# esp-rfid-relay-board.net
KiCad netlist of a schematic drawn in EAGLE
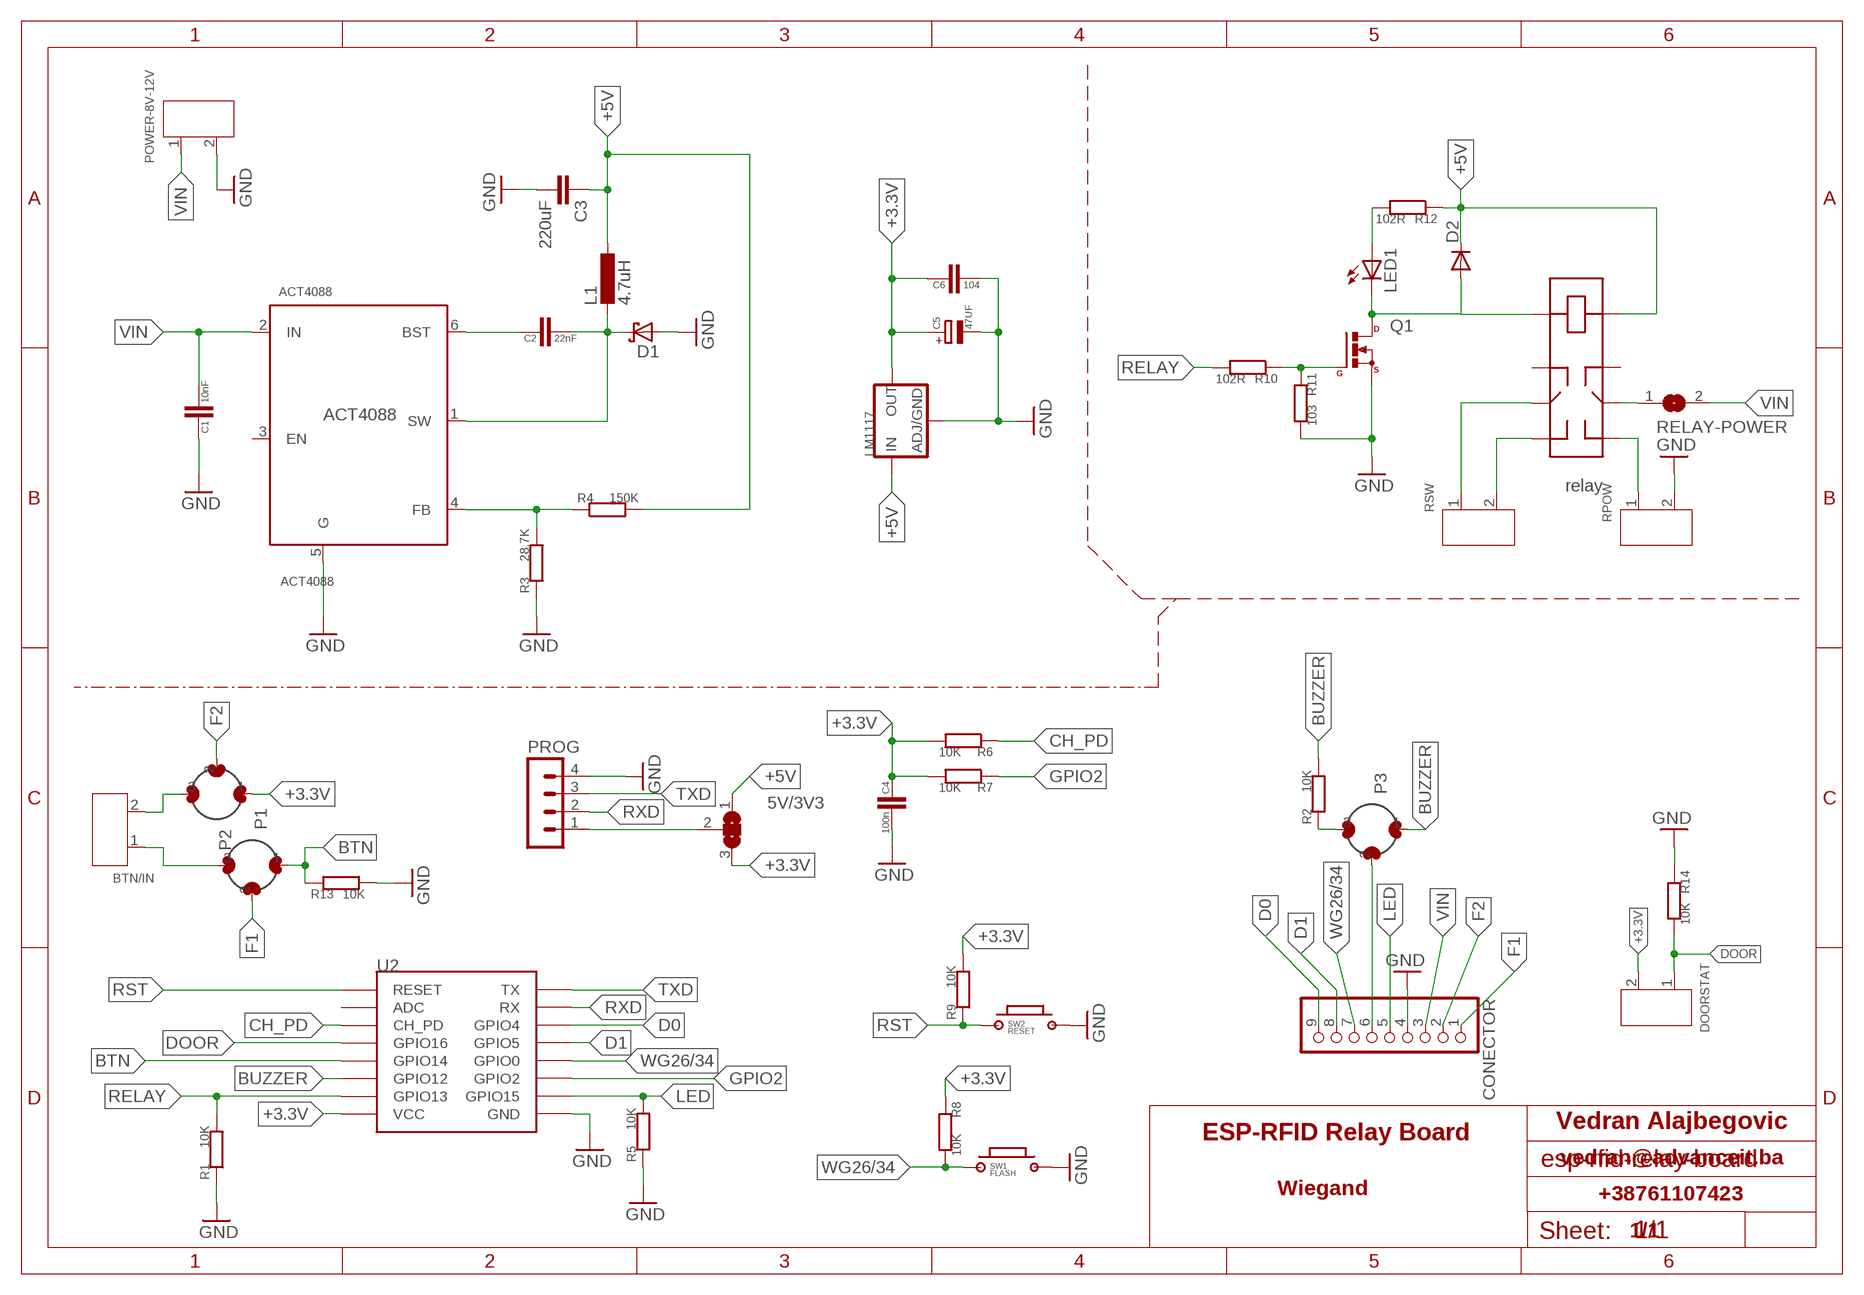
[diagram p0: schematic, sheet 1]

(export (version "E")
  (design (tool "Eeschema 10.0.6"))
  (components
    (comp (ref "5V/3V3")
      (value "SJ2W")
      (footprint "eagle-import:SJ_2")
      (libsource (lib "eagle-import") (part "SJ2W"))
    )
    (comp (ref "ACT4088")
      (value "ACT4088")
      (footprint "eagle-import:SOT-23-6")
      (fields (field (name "MPN") "AIC1896CG"))
      (libsource (lib "eagle-import") (part "ACT4088-(SOT23-6)"))
    )
    (comp (ref "BTN/IN")
      (value "SCREW-TERMINAL-GREEN(2P-3.5)")
      (footprint "eagle-import:H2-3.5-7.0X7.0MM")
      (libsource (lib "eagle-import") (part "SCREW-TERMINAL-GREEN(2P-3.5)"))
    )
    (comp (ref "C1")
      (value "10nF")
      (footprint "eagle-import:C_0805")
      (libsource (lib "eagle-import") (part "CAPC0805"))
    )
    (comp (ref "C2")
      (value "22nF")
      (footprint "eagle-import:C_0805")
      (libsource (lib "eagle-import") (part "CAPC0805"))
    )
    (comp (ref "C3")
      (value "220uF")
      (footprint "eagle-import:C1210")
      (libsource (lib "eagle-import") (part "C-EUC1210"))
    )
    (comp (ref "C4")
      (value "100n")
      (footprint "eagle-import:C_0805")
      (libsource (lib "eagle-import") (part "CAPC0805"))
    )
    (comp (ref "C5")
      (value "47UF")
      (footprint "eagle-import:CPOL_B3528")
      (libsource (lib "eagle-import") (part "CPOLB_3528"))
    )
    (comp (ref "C6")
      (value "104")
      (footprint "eagle-import:C_0805")
      (libsource (lib "eagle-import") (part "CAPC0805"))
    )
    (comp (ref "CONECTOR")
      (value "PINHD-1X9")
      (footprint "eagle-import:1X09")
      (libsource (lib "eagle-import") (part "PINHD-1X9"))
    )
    (comp (ref "D1")
      (value "SCHOTTKY-DIODESMD")
      (footprint "eagle-import:SMB")
      (libsource (lib "eagle-import") (part "SCHOTTKY-DIODESMD"))
    )
    (comp (ref "D2")
      (value "4007-4148")
      (footprint "eagle-import:DIO_SOD123FL")
      (libsource (lib "eagle-import") (part "DIODESOD123FL"))
    )
    (comp (ref "DOORSTAT")
      (value "SCREW-TERMINAL-GREEN(2P-3.5)")
      (footprint "eagle-import:H2-3.5-7.0X7.0MM")
      (libsource (lib "eagle-import") (part "SCREW-TERMINAL-GREEN(2P-3.5)"))
    )
    (comp (ref "L1")
      (value "4.7uH")
      (footprint "eagle-import:L3225M")
      (libsource (lib "eagle-import") (part "L-EUL3225M"))
    )
    (comp (ref "LED1")
      (value "LED0805LED")
      (footprint "eagle-import:0805LED")
      (libsource (lib "eagle-import") (part "LED0805LED"))
    )
    (comp (ref "LM1117")
      (value "POWERSOT223")
      (footprint "eagle-import:SOT223")
      (libsource (lib "eagle-import") (part "POWERSOT223"))
    )
    (comp (ref "P1")
      (value "SJ3")
      (footprint "eagle-import:SJ_3")
      (libsource (lib "eagle-import") (part "SJ3"))
    )
    (comp (ref "P2")
      (value "SJ3")
      (footprint "eagle-import:SJ_3")
      (libsource (lib "eagle-import") (part "SJ3"))
    )
    (comp (ref "P3")
      (value "SJ3")
      (footprint "eagle-import:SJ_3")
      (libsource (lib "eagle-import") (part "SJ3"))
    )
    (comp (ref "POWER-8V-12V")
      (value "SCREW-TERMINAL-GREEN(2P-3.5)")
      (footprint "eagle-import:H2-3.5-7.0X7.0MM")
      (libsource (lib "eagle-import") (part "SCREW-TERMINAL-GREEN(2P-3.5)"))
    )
    (comp (ref "PROG")
      (value "MA04-1")
      (footprint "eagle-import:MA04-1")
      (libsource (lib "eagle-import") (part "MA04-1"))
    )
    (comp (ref "Q1")
      (value "MOSFET_NSOT23")
      (footprint "eagle-import:SOT23")
      (libsource (lib "eagle-import") (part "MOSFET_NSOT23"))
    )
    (comp (ref "R1")
      (value "10K")
      (footprint "eagle-import:R_0805")
      (libsource (lib "eagle-import") (part "RESISTORR0805"))
    )
    (comp (ref "R2")
      (value "10K")
      (footprint "eagle-import:R_0805")
      (libsource (lib "eagle-import") (part "RESISTORR0805"))
    )
    (comp (ref "R3")
      (value "28.7K")
      (footprint "eagle-import:R_0805")
      (libsource (lib "eagle-import") (part "RESISTORR0805"))
    )
    (comp (ref "R4")
      (value "150K")
      (footprint "eagle-import:R_0805")
      (libsource (lib "eagle-import") (part "RESISTORR0805"))
    )
    (comp (ref "R5")
      (value "10K")
      (footprint "eagle-import:R_0805")
      (libsource (lib "eagle-import") (part "RESISTORR0805"))
    )
    (comp (ref "R6")
      (value "10K")
      (footprint "eagle-import:R_0805")
      (libsource (lib "eagle-import") (part "RESISTORR0805"))
    )
    (comp (ref "R7")
      (value "10K")
      (footprint "eagle-import:R_0805")
      (libsource (lib "eagle-import") (part "RESISTORR0805"))
    )
    (comp (ref "R8")
      (value "10K")
      (footprint "eagle-import:R_0805")
      (libsource (lib "eagle-import") (part "RESISTORR0805"))
    )
    (comp (ref "R9")
      (value "10K")
      (footprint "eagle-import:R_0805")
      (libsource (lib "eagle-import") (part "RESISTORR0805"))
    )
    (comp (ref "R10")
      (value "102R")
      (footprint "eagle-import:R_0805")
      (libsource (lib "eagle-import") (part "RESISTORR0805"))
    )
    (comp (ref "R11")
      (value "103")
      (footprint "eagle-import:R_0805")
      (libsource (lib "eagle-import") (part "RESISTORR0805"))
    )
    (comp (ref "R12")
      (value "102R")
      (footprint "eagle-import:R_0805")
      (libsource (lib "eagle-import") (part "RESISTORR0805"))
    )
    (comp (ref "R13")
      (value "10K")
      (footprint "eagle-import:R_0805")
      (libsource (lib "eagle-import") (part "RESISTORR0805"))
    )
    (comp (ref "R14")
      (value "10K")
      (footprint "eagle-import:R_0805")
      (libsource (lib "eagle-import") (part "RESISTORR0805"))
    )
    (comp (ref "RELAY")
      (value "2XSWITCH")
      (footprint "eagle-import:HFD3-SIGNAL")
      (libsource (lib "eagle-import") (part "2XSWITCH"))
    )
    (comp (ref "RELAY-POWER")
      (value "SJ")
      (footprint "eagle-import:SJ")
      (libsource (lib "eagle-import") (part "SJ"))
    )
    (comp (ref "RPOW")
      (value "SCREW-TERMINAL-GREEN(2P-3.5)")
      (footprint "eagle-import:H2-3.5-7.0X7.0MM")
      (libsource (lib "eagle-import") (part "SCREW-TERMINAL-GREEN(2P-3.5)"))
    )
    (comp (ref "RSW")
      (value "SCREW-TERMINAL-GREEN(2P-3.5)")
      (footprint "eagle-import:H2-3.5-7.0X7.0MM")
      (libsource (lib "eagle-import") (part "SCREW-TERMINAL-GREEN(2P-3.5)"))
    )
    (comp (ref "SW1")
      (value "FLASH")
      (footprint "eagle-import:2P-SWITCH-TURTLE")
      (libsource (lib "eagle-import") (part "BUTTON-2PSWITCH-TURTLE-2P"))
    )
    (comp (ref "SW2")
      (value "RESET")
      (footprint "eagle-import:2P-SWITCH-TURTLE")
      (libsource (lib "eagle-import") (part "BUTTON-2PSWITCH-TURTLE-2P"))
    )
    (comp (ref "U2")
      (value "ESP12SMD")
      (footprint "eagle-import:ESP12-SMD")
      (libsource (lib "eagle-import") (part "ESP12SMD"))
    )
  )
  (nets
    (net (code "1") (name "+3.3V") (class "Default")
      (node (ref "5V/3V3") (pin "3") (pinfunction "3_3") (pintype "passive"))
      (node (ref "C4") (pin "1") (pinfunction "1_1") (pintype "passive"))
      (node (ref "C5") (pin "+") (pinfunction "+_+") (pintype "passive"))
      (node (ref "C6") (pin "1") (pinfunction "1_1") (pintype "passive"))
      (node (ref "DOORSTAT") (pin "2") (pinfunction "2_2") (pintype "bidirectional"))
      (node (ref "LM1117") (pin "OUT1") (pinfunction "OUT_OUT1") (pintype "output"))
      (node (ref "LM1117") (pin "OUT2") (pinfunction "OUT_OUT2") (pintype "output"))
      (node (ref "P2") (pin "1") (pinfunction "1_1") (pintype "passive"))
      (node (ref "R6") (pin "2") (pinfunction "2_2") (pintype "passive"))
      (node (ref "R7") (pin "2") (pinfunction "2_2") (pintype "passive"))
      (node (ref "R8") (pin "1") (pinfunction "1_1") (pintype "passive"))
      (node (ref "R9") (pin "2") (pinfunction "2_2") (pintype "passive"))
      (node (ref "U2") (pin "VCC") (pinfunction "VCC_VCC") (pintype "bidirectional"))
    )
    (net (code "2") (name "+5V") (class "Default")
      (node (ref "5V/3V3") (pin "1") (pinfunction "1_1") (pintype "passive"))
      (node (ref "C3") (pin "1") (pinfunction "1_1") (pintype "passive"))
      (node (ref "D2") (pin "C") (pinfunction "C_C") (pintype "passive"))
      (node (ref "L1") (pin "1") (pinfunction "1_1") (pintype "passive"))
      (node (ref "LM1117") (pin "IN+") (pinfunction "IN_IN+") (pintype "input"))
      (node (ref "R12") (pin "1") (pinfunction "1_1") (pintype "passive"))
      (node (ref "R4") (pin "2") (pinfunction "2_2") (pintype "passive"))
      (node (ref "RELAY") (pin "8") (pinfunction "8_8") (pintype "bidirectional"))
    )
    (net (code "3") (name "BTN") (class "Default")
      (node (ref "P1") (pin "1") (pinfunction "1_1") (pintype "passive"))
      (node (ref "R13") (pin "1") (pinfunction "1_1") (pintype "passive"))
      (node (ref "U2") (pin "GPIO14") (pinfunction "GPIO14_GPIO14") (pintype "bidirectional"))
    )
    (net (code "4") (name "BUZZER") (class "Default")
      (node (ref "P3") (pin "1") (pinfunction "1_1") (pintype "passive"))
      (node (ref "R2") (pin "2") (pinfunction "2_2") (pintype "passive"))
      (node (ref "U2") (pin "GPIO12") (pinfunction "GPIO12_GPIO12") (pintype "bidirectional"))
    )
    (net (code "5") (name "CH_PD") (class "Default")
      (node (ref "R6") (pin "1") (pinfunction "1_1") (pintype "passive"))
      (node (ref "U2") (pin "CH_PD") (pinfunction "CH_PD_CH_PD") (pintype "bidirectional"))
    )
    (net (code "6") (name "D0") (class "Default")
      (node (ref "CONECTOR") (pin "9") (pinfunction "9_9") (pintype "passive"))
      (node (ref "U2") (pin "GPIO4") (pinfunction "GPIO4_GPIO4") (pintype "bidirectional"))
    )
    (net (code "7") (name "D1") (class "Default")
      (node (ref "CONECTOR") (pin "8") (pinfunction "8_8") (pintype "passive"))
      (node (ref "U2") (pin "GPIO5") (pinfunction "GPIO5_GPIO5") (pintype "bidirectional"))
    )
    (net (code "8") (name "DOOR") (class "Default")
      (node (ref "DOORSTAT") (pin "1") (pinfunction "1_1") (pintype "bidirectional"))
      (node (ref "R14") (pin "2") (pinfunction "2_2") (pintype "passive"))
      (node (ref "U2") (pin "GPIO16") (pinfunction "GPIO16_GPIO16") (pintype "bidirectional"))
    )
    (net (code "9") (name "F1") (class "Default")
      (node (ref "CONECTOR") (pin "1") (pinfunction "1_1") (pintype "passive"))
      (node (ref "P1") (pin "2") (pinfunction "2_2") (pintype "passive"))
    )
    (net (code "10") (name "F2") (class "Default")
      (node (ref "CONECTOR") (pin "2") (pinfunction "2_2") (pintype "passive"))
      (node (ref "P2") (pin "2") (pinfunction "2_2") (pintype "passive"))
    )
    (net (code "11") (name "GND") (class "Default")
      (node (ref "ACT4088") (pin "5") (pinfunction "G_5") (pintype "input"))
      (node (ref "C1") (pin "1") (pinfunction "1_1") (pintype "passive"))
      (node (ref "C3") (pin "2") (pinfunction "2_2") (pintype "passive"))
      (node (ref "C4") (pin "2") (pinfunction "2_2") (pintype "passive"))
      (node (ref "C5") (pin "-") (pinfunction "-_-") (pintype "passive"))
      (node (ref "C6") (pin "2") (pinfunction "2_2") (pintype "passive"))
      (node (ref "CONECTOR") (pin "4") (pinfunction "4_4") (pintype "passive"))
      (node (ref "D1") (pin "A") (pinfunction "A_A") (pintype "passive"))
      (node (ref "LM1117") (pin "GND") (pinfunction "GND_GND") (pintype "input"))
      (node (ref "POWER-8V-12V") (pin "2") (pinfunction "2_2") (pintype "bidirectional"))
      (node (ref "PROG") (pin "4") (pinfunction "4_4") (pintype "passive"))
      (node (ref "Q1") (pin "2") (pinfunction "S_2") (pintype "passive"))
      (node (ref "R1") (pin "1") (pinfunction "1_1") (pintype "passive"))
      (node (ref "R11") (pin "2") (pinfunction "2_2") (pintype "passive"))
      (node (ref "R13") (pin "2") (pinfunction "2_2") (pintype "passive"))
      (node (ref "R14") (pin "1") (pinfunction "1_1") (pintype "passive"))
      (node (ref "R3") (pin "1") (pinfunction "1_1") (pintype "passive"))
      (node (ref "R5") (pin "1") (pinfunction "1_1") (pintype "passive"))
      (node (ref "RPOW") (pin "2") (pinfunction "2_2") (pintype "bidirectional"))
      (node (ref "SW1") (pin "2") (pinfunction "P$2_2") (pintype "bidirectional"))
      (node (ref "SW2") (pin "2") (pinfunction "P$2_2") (pintype "bidirectional"))
      (node (ref "U2") (pin "GND") (pinfunction "GND_GND") (pintype "bidirectional"))
    )
    (net (code "12") (name "GPIO2") (class "Default")
      (node (ref "R7") (pin "1") (pinfunction "1_1") (pintype "passive"))
      (node (ref "U2") (pin "GPIO2") (pinfunction "GPIO2_GPIO2") (pintype "bidirectional"))
    )
    (net (code "13") (name "LED") (class "Default")
      (node (ref "CONECTOR") (pin "5") (pinfunction "5_5") (pintype "passive"))
      (node (ref "R5") (pin "2") (pinfunction "2_2") (pintype "passive"))
      (node (ref "U2") (pin "GPIO15") (pinfunction "GPIO15_GPIO15") (pintype "bidirectional"))
    )
    (net (code "14") (name "Net-(5V/3V3-Pad2)") (class "Default")
      (node (ref "5V/3V3") (pin "2") (pinfunction "2_2") (pintype "passive"))
      (node (ref "PROG") (pin "1") (pinfunction "1_1") (pintype "passive"))
    )
    (net (code "15") (name "Net-(ACT4088-BST)") (class "Default")
      (node (ref "ACT4088") (pin "6") (pinfunction "BST_6") (pintype "output"))
      (node (ref "C2") (pin "1") (pinfunction "1_1") (pintype "passive"))
    )
    (net (code "16") (name "Net-(ACT4088-FB)") (class "Default")
      (node (ref "ACT4088") (pin "4") (pinfunction "FB_4") (pintype "power_in"))
      (node (ref "R3") (pin "2") (pinfunction "2_2") (pintype "passive"))
      (node (ref "R4") (pin "1") (pinfunction "1_1") (pintype "passive"))
    )
    (net (code "17") (name "Net-(ACT4088-SW)") (class "Default")
      (node (ref "ACT4088") (pin "1") (pinfunction "SW_1") (pintype "input"))
      (node (ref "C2") (pin "2") (pinfunction "2_2") (pintype "passive"))
      (node (ref "D1") (pin "C") (pinfunction "C_C") (pintype "passive"))
      (node (ref "L1") (pin "2") (pinfunction "2_2") (pintype "passive"))
    )
    (net (code "18") (name "Net-(BTN/IN-Pad1)") (class "Default")
      (node (ref "BTN/IN") (pin "1") (pinfunction "1_1") (pintype "bidirectional"))
      (node (ref "P1") (pin "3") (pinfunction "3_3") (pintype "passive"))
    )
    (net (code "19") (name "Net-(BTN/IN-Pad2)") (class "Default")
      (node (ref "BTN/IN") (pin "2") (pinfunction "2_2") (pintype "bidirectional"))
      (node (ref "P2") (pin "3") (pinfunction "3_3") (pintype "passive"))
    )
    (net (code "20") (name "Net-(CONECTOR-Pad6)") (class "Default")
      (node (ref "CONECTOR") (pin "6") (pinfunction "6_6") (pintype "passive"))
      (node (ref "P3") (pin "2") (pinfunction "2_2") (pintype "passive"))
    )
    (net (code "21") (name "Net-(LED1-PadA)") (class "Default")
      (node (ref "LED1") (pin "A") (pinfunction "A_A") (pintype "passive"))
      (node (ref "R12") (pin "2") (pinfunction "2_2") (pintype "passive"))
    )
    (net (code "22") (name "Net-(P3-Pad3)") (class "Default")
      (node (ref "P3") (pin "3") (pinfunction "3_3") (pintype "passive"))
      (node (ref "R2") (pin "1") (pinfunction "1_1") (pintype "passive"))
    )
    (net (code "23") (name "Net-(Q1-D)") (class "Default")
      (node (ref "D2") (pin "A") (pinfunction "A_A") (pintype "passive"))
      (node (ref "LED1") (pin "C") (pinfunction "C_C") (pintype "passive"))
      (node (ref "Q1") (pin "3") (pinfunction "D_3") (pintype "passive"))
      (node (ref "RELAY") (pin "1") (pinfunction "1_1") (pintype "bidirectional"))
    )
    (net (code "24") (name "Net-(Q1-G)") (class "Default")
      (node (ref "Q1") (pin "1") (pinfunction "G_1") (pintype "passive"))
      (node (ref "R10") (pin "1") (pinfunction "1_1") (pintype "passive"))
      (node (ref "R11") (pin "1") (pinfunction "1_1") (pintype "passive"))
    )
    (net (code "25") (name "Net-(RELAY-POWER-Pad1)") (class "Default")
      (node (ref "RELAY") (pin "6") (pinfunction "6_6") (pintype "bidirectional"))
      (node (ref "RELAY-POWER") (pin "1") (pinfunction "1_1") (pintype "passive"))
    )
    (net (code "26") (name "Net-(RELAY-Pad3)") (class "Default")
      (node (ref "RELAY") (pin "3") (pinfunction "3_3") (pintype "bidirectional"))
      (node (ref "RSW") (pin "1") (pinfunction "1_1") (pintype "bidirectional"))
    )
    (net (code "27") (name "Net-(RELAY-Pad4)") (class "Default")
      (node (ref "RELAY") (pin "4") (pinfunction "4_4") (pintype "bidirectional"))
      (node (ref "RSW") (pin "2") (pinfunction "2_2") (pintype "bidirectional"))
    )
    (net (code "28") (name "Net-(RELAY-Pad5)") (class "Default")
      (node (ref "RELAY") (pin "5") (pinfunction "5_5") (pintype "bidirectional"))
      (node (ref "RPOW") (pin "1") (pinfunction "1_1") (pintype "bidirectional"))
    )
    (net (code "29") (name "RELAY") (class "Default")
      (node (ref "R1") (pin "2") (pinfunction "2_2") (pintype "passive"))
      (node (ref "R10") (pin "2") (pinfunction "2_2") (pintype "passive"))
      (node (ref "U2") (pin "GPIO13") (pinfunction "GPIO13_GPIO13") (pintype "bidirectional"))
    )
    (net (code "30") (name "RST") (class "Default")
      (node (ref "R9") (pin "1") (pinfunction "1_1") (pintype "passive"))
      (node (ref "SW2") (pin "1") (pinfunction "P$1_1") (pintype "bidirectional"))
      (node (ref "U2") (pin "RESET") (pinfunction "RESET_RESET") (pintype "bidirectional"))
    )
    (net (code "31") (name "RXD") (class "Default")
      (node (ref "PROG") (pin "2") (pinfunction "2_2") (pintype "passive"))
      (node (ref "U2") (pin "RXD0") (pinfunction "RX_RXD0") (pintype "bidirectional"))
    )
    (net (code "32") (name "TXD") (class "Default")
      (node (ref "PROG") (pin "3") (pinfunction "3_3") (pintype "passive"))
      (node (ref "U2") (pin "TXD0") (pinfunction "TX_TXD0") (pintype "bidirectional"))
    )
    (net (code "33") (name "VIN") (class "Default")
      (node (ref "ACT4088") (pin "2") (pinfunction "IN_2") (pintype "input"))
      (node (ref "C1") (pin "2") (pinfunction "2_2") (pintype "passive"))
      (node (ref "CONECTOR") (pin "3") (pinfunction "3_3") (pintype "passive"))
      (node (ref "POWER-8V-12V") (pin "1") (pinfunction "1_1") (pintype "bidirectional"))
      (node (ref "RELAY-POWER") (pin "2") (pinfunction "2_2") (pintype "passive"))
    )
    (net (code "34") (name "WG26{slash}34") (class "Default")
      (node (ref "CONECTOR") (pin "7") (pinfunction "7_7") (pintype "passive"))
      (node (ref "R8") (pin "2") (pinfunction "2_2") (pintype "passive"))
      (node (ref "SW1") (pin "1") (pinfunction "P$1_1") (pintype "bidirectional"))
      (node (ref "U2") (pin "GPIO0") (pinfunction "GPIO0_GPIO0") (pintype "bidirectional"))
    )
    (net (code "35") (name "unconnected-(ACT4088-EN-Pad3)") (class "Default")
      (node (ref "ACT4088") (pin "3") (pinfunction "EN_3") (pintype "input"))
    )
    (net (code "36") (name "unconnected-(RELAY-Pad2)") (class "Default")
      (node (ref "RELAY") (pin "2") (pinfunction "2_2") (pintype "bidirectional"))
    )
    (net (code "37") (name "unconnected-(RELAY-Pad7)") (class "Default")
      (node (ref "RELAY") (pin "7") (pinfunction "7_7") (pintype "bidirectional"))
    )
    (net (code "38") (name "unconnected-(U2-PadADC)") (class "Default")
      (node (ref "U2") (pin "ADC") (pinfunction "ADC_ADC") (pintype "bidirectional"))
    )
  )
)
